# TSS_Rev3_Shield.net
KiCad netlist of a schematic drawn in EAGLE
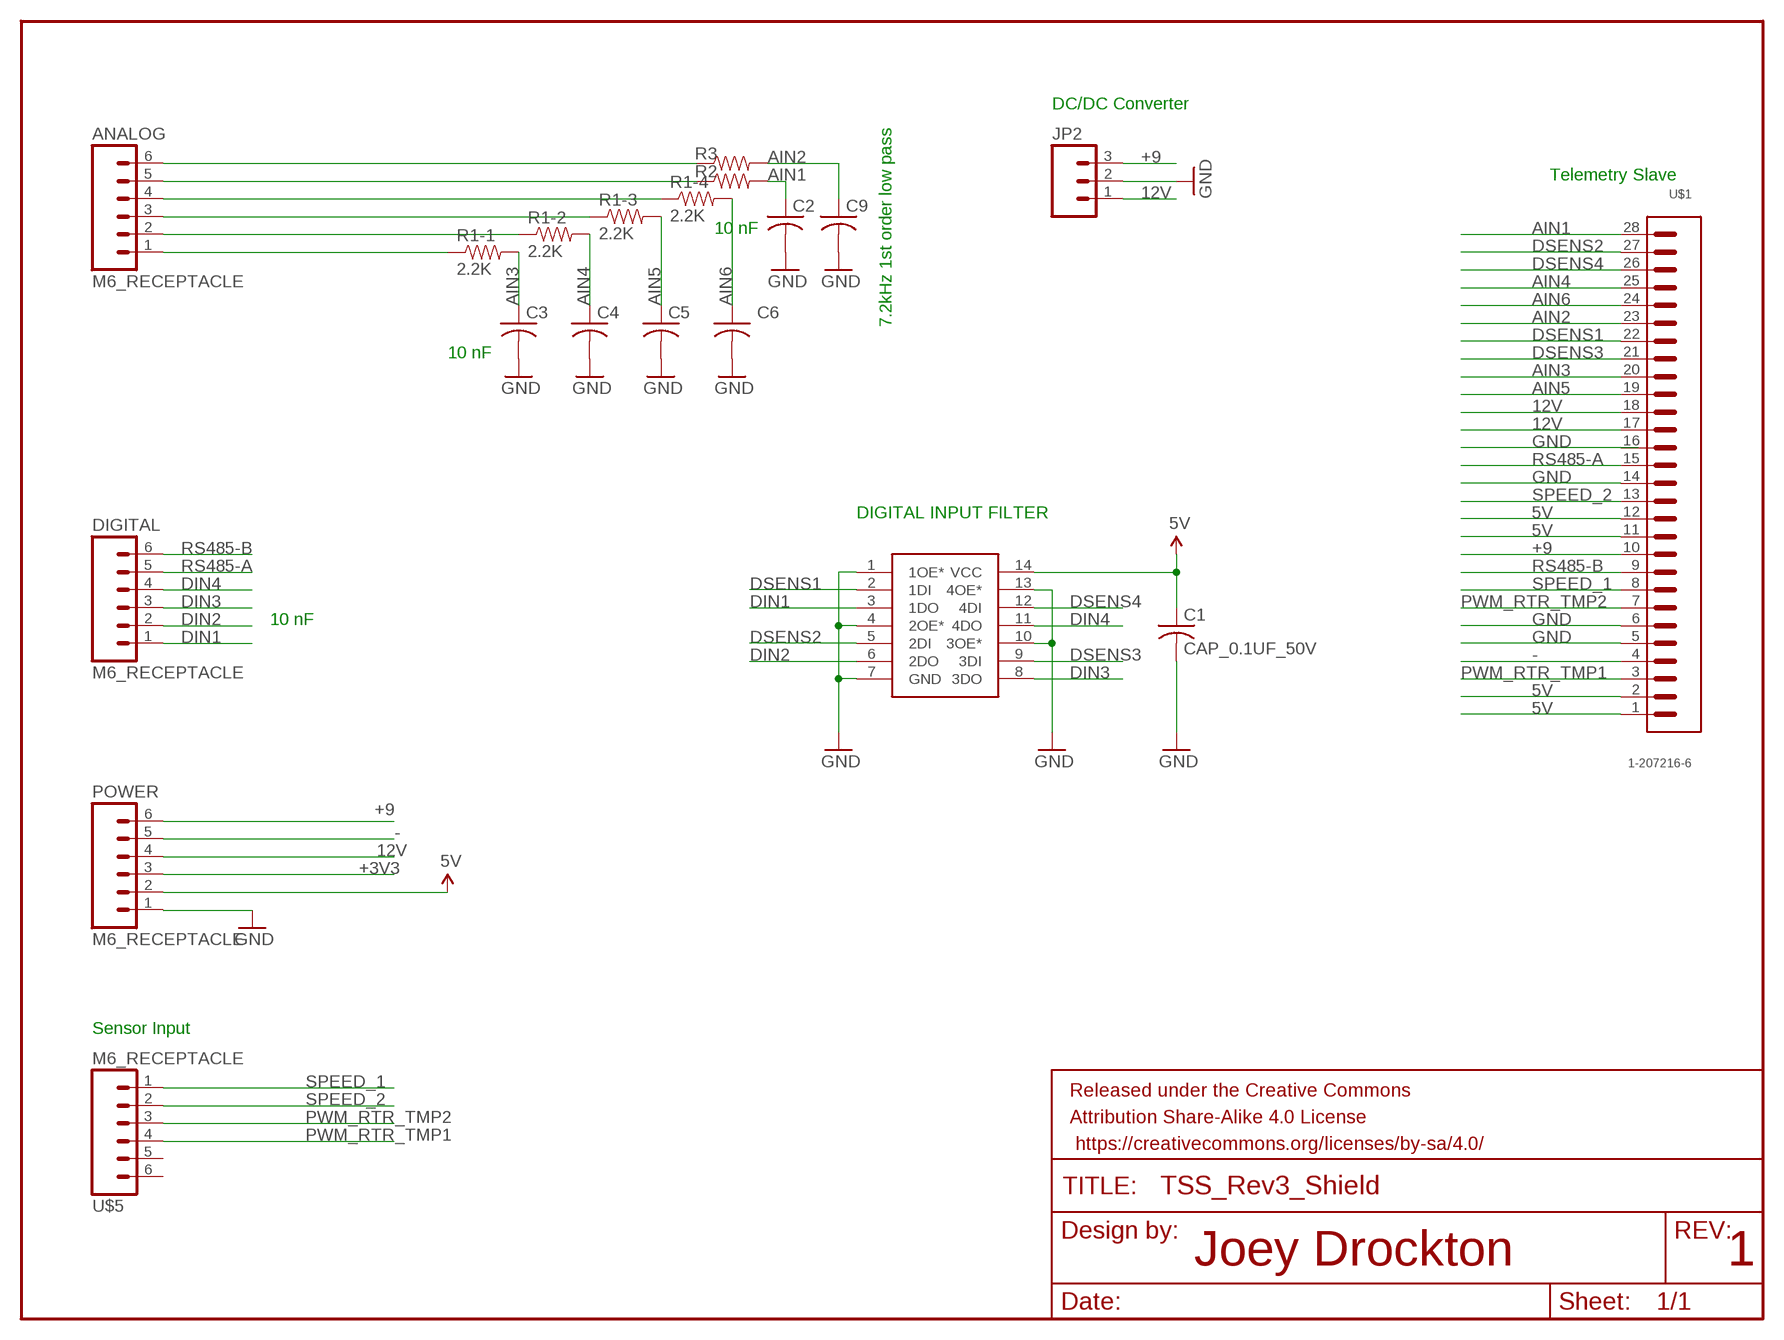
[diagram p0: schematic, sheet 1]

(export (version "E")
  (design (tool "Eeschema 10.0.6"))
  (components
    (comp (ref "ANALOG")
      (value "M6_RECEPTACLE")
      (footprint "eagle-import:6X.1")
      (fields (field (name "PARTNO") "A32907-ND"))
      (libsource (lib "eagle-import") (part "M6_RECEPTACLE"))
    )
    (comp (ref "C1")
      (value "CAP_0.1UF_50V")
      (footprint "eagle-import:0603")
      (fields (field (name "PARTNO") "CC0603ZRY5V9BB104"))
      (libsource (lib "eagle-import") (part "CAP_0.1UF_50V"))
    )
    (comp (ref "C2")
      (value "CAP_10NF_50V")
      (footprint "eagle-import:0603")
      (fields (field (name "PARTNO") "CL10F103ZB8NNNC"))
      (libsource (lib "eagle-import") (part "CAP_10NF_50V"))
    )
    (comp (ref "C3")
      (value "CAP_10NF_50V")
      (footprint "eagle-import:0603")
      (fields (field (name "PARTNO") "CL10F103ZB8NNNC"))
      (libsource (lib "eagle-import") (part "CAP_10NF_50V"))
    )
    (comp (ref "C4")
      (value "CAP_10NF_50V")
      (footprint "eagle-import:0603")
      (fields (field (name "PARTNO") "CL10F103ZB8NNNC"))
      (libsource (lib "eagle-import") (part "CAP_10NF_50V"))
    )
    (comp (ref "C5")
      (value "CAP_10NF_50V")
      (footprint "eagle-import:0603")
      (fields (field (name "PARTNO") "CL10F103ZB8NNNC"))
      (libsource (lib "eagle-import") (part "CAP_10NF_50V"))
    )
    (comp (ref "C6")
      (value "CAP_10NF_50V")
      (footprint "eagle-import:0603")
      (fields (field (name "PARTNO") "CL10F103ZB8NNNC"))
      (libsource (lib "eagle-import") (part "CAP_10NF_50V"))
    )
    (comp (ref "C9")
      (value "CAP_10NF_50V")
      (footprint "eagle-import:0603")
      (fields (field (name "PARTNO") "CL10F103ZB8NNNC"))
      (libsource (lib "eagle-import") (part "CAP_10NF_50V"))
    )
    (comp (ref "DIGITAL")
      (value "M6_RECEPTACLE")
      (footprint "eagle-import:6X.1")
      (fields (field (name "PARTNO") "A32907-ND"))
      (libsource (lib "eagle-import") (part "M6_RECEPTACLE"))
    )
    (comp (ref "FRAME1")
      (value "FRAME-LETTERNO_PACKAGE")
      (footprint "eagle-import:DUMMY")
      (fields (field (name "DESIGNER") "Nobody"))
      (libsource (lib "eagle-import") (part "FRAME-LETTERNO_PACKAGE"))
    )
    (comp (ref "JP2")
      (value "M03PTH")
      (footprint "eagle-import:1X03")
      (libsource (lib "eagle-import") (part "M03PTH"))
    )
    (comp (ref "POWER")
      (value "M6_RECEPTACLE")
      (footprint "eagle-import:6X.1")
      (fields (field (name "PARTNO") "A32907-ND"))
      (libsource (lib "eagle-import") (part "M6_RECEPTACLE"))
    )
    (comp (ref "R1")
      (value "2.2K")
      (footprint "eagle-import:MNR14")
      (fields (field (name "PARTNO") "MNR14ERAPJ222"))
      (libsource (lib "eagle-import") (part "RN-4_2.2K"))
    )
    (comp (ref "R2")
      (value "RES_2.2K_1%")
      (footprint "eagle-import:0603")
      (fields (field (name "PARTNO") "RC0603FR-072K2L"))
      (libsource (lib "eagle-import") (part "RES_2.2K_1%"))
    )
    (comp (ref "R3")
      (value "RES_2.2K_1%")
      (footprint "eagle-import:0603")
      (fields (field (name "PARTNO") "RC0603FR-072K2L"))
      (libsource (lib "eagle-import") (part "RES_2.2K_1%"))
    )
    (comp (ref "U$1")
      (value "1-207216-6")
      (footprint "eagle-import:1-207216-6")
      (libsource (lib "eagle-import") (part "1-207216-6"))
    )
    (comp (ref "U$2")
      (value "74HC125S14-13")
      (footprint "eagle-import:SO-14")
      (fields (field (name "PARTNO") " 74HC125S14-13DICT-ND"))
      (libsource (lib "eagle-import") (part "74HC125S14-13"))
    )
    (comp (ref "U$5")
      (value "M6_RECEPTACLE")
      (footprint "eagle-import:6X.1")
      (fields (field (name "PARTNO") "A32907-ND"))
      (libsource (lib "eagle-import") (part "M6_RECEPTACLE"))
    )
  )
  (nets
    (net (code "1") (name "/+3V3") (class "Default")
      (node (ref "POWER") (pin "3") (pinfunction "3_3") (pintype "passive"))
    )
    (net (code "2") (name "/+9") (class "Default")
      (node (ref "JP2") (pin "3") (pinfunction "3_3") (pintype "passive"))
      (node (ref "POWER") (pin "6") (pinfunction "6_6") (pintype "passive"))
      (node (ref "U$1") (pin "10") (pinfunction "P$10_10") (pintype "bidirectional"))
    )
    (net (code "3") (name "/-") (class "Default")
      (node (ref "POWER") (pin "5") (pinfunction "5_5") (pintype "passive"))
      (node (ref "U$1") (pin "4") (pinfunction "P$4_4") (pintype "bidirectional"))
    )
    (net (code "4") (name "/12V") (class "Default")
      (node (ref "JP2") (pin "1") (pinfunction "1_1") (pintype "passive"))
      (node (ref "POWER") (pin "4") (pinfunction "4_4") (pintype "passive"))
      (node (ref "U$1") (pin "17") (pinfunction "P$17_17") (pintype "bidirectional"))
      (node (ref "U$1") (pin "18") (pinfunction "P$18_18") (pintype "bidirectional"))
    )
    (net (code "5") (name "/AIN1") (class "Default")
      (node (ref "C2") (pin "1") (pinfunction "+_1") (pintype "passive"))
      (node (ref "R2") (pin "2") (pinfunction "2_2") (pintype "passive"))
      (node (ref "U$1") (pin "28") (pinfunction "P$28_28") (pintype "bidirectional"))
    )
    (net (code "6") (name "/AIN2") (class "Default")
      (node (ref "C9") (pin "1") (pinfunction "+_1") (pintype "passive"))
      (node (ref "R3") (pin "2") (pinfunction "2_2") (pintype "passive"))
      (node (ref "U$1") (pin "23") (pinfunction "P$23_23") (pintype "bidirectional"))
    )
    (net (code "7") (name "/AIN3") (class "Default")
      (node (ref "C3") (pin "1") (pinfunction "+_1") (pintype "passive"))
      (node (ref "R1") (pin "8") (pinfunction "2_8") (pintype "passive"))
      (node (ref "U$1") (pin "20") (pinfunction "P$20_20") (pintype "bidirectional"))
    )
    (net (code "8") (name "/AIN4") (class "Default")
      (node (ref "C4") (pin "1") (pinfunction "+_1") (pintype "passive"))
      (node (ref "R1") (pin "7") (pinfunction "2_7") (pintype "passive"))
      (node (ref "U$1") (pin "25") (pinfunction "P$25_25") (pintype "bidirectional"))
    )
    (net (code "9") (name "/AIN5") (class "Default")
      (node (ref "C5") (pin "1") (pinfunction "+_1") (pintype "passive"))
      (node (ref "R1") (pin "6") (pinfunction "2_6") (pintype "passive"))
      (node (ref "U$1") (pin "19") (pinfunction "P$19_19") (pintype "bidirectional"))
    )
    (net (code "10") (name "/AIN6") (class "Default")
      (node (ref "C6") (pin "1") (pinfunction "+_1") (pintype "passive"))
      (node (ref "R1") (pin "5") (pinfunction "2_5") (pintype "passive"))
      (node (ref "U$1") (pin "24") (pinfunction "P$24_24") (pintype "bidirectional"))
    )
    (net (code "11") (name "/DIN1") (class "Default")
      (node (ref "DIGITAL") (pin "1") (pinfunction "1_1") (pintype "passive"))
      (node (ref "U$2") (pin "3") (pinfunction "1DO_3") (pintype "bidirectional"))
    )
    (net (code "12") (name "/DIN2") (class "Default")
      (node (ref "DIGITAL") (pin "2") (pinfunction "2_2") (pintype "passive"))
      (node (ref "U$2") (pin "6") (pinfunction "2DO_6") (pintype "bidirectional"))
    )
    (net (code "13") (name "/DIN3") (class "Default")
      (node (ref "DIGITAL") (pin "3") (pinfunction "3_3") (pintype "passive"))
      (node (ref "U$2") (pin "8") (pinfunction "3DO_8") (pintype "bidirectional"))
    )
    (net (code "14") (name "/DIN4") (class "Default")
      (node (ref "DIGITAL") (pin "4") (pinfunction "4_4") (pintype "passive"))
      (node (ref "U$2") (pin "11") (pinfunction "4DO_11") (pintype "bidirectional"))
    )
    (net (code "15") (name "/DSENS1") (class "Default")
      (node (ref "U$1") (pin "22") (pinfunction "P$22_22") (pintype "bidirectional"))
      (node (ref "U$2") (pin "2") (pinfunction "1DI_2") (pintype "bidirectional"))
    )
    (net (code "16") (name "/DSENS2") (class "Default")
      (node (ref "U$1") (pin "27") (pinfunction "P$27_27") (pintype "bidirectional"))
      (node (ref "U$2") (pin "5") (pinfunction "2DI_5") (pintype "bidirectional"))
    )
    (net (code "17") (name "/DSENS3") (class "Default")
      (node (ref "U$1") (pin "21") (pinfunction "P$21_21") (pintype "bidirectional"))
      (node (ref "U$2") (pin "9") (pinfunction "3DI_9") (pintype "bidirectional"))
    )
    (net (code "18") (name "/DSENS4") (class "Default")
      (node (ref "U$1") (pin "26") (pinfunction "P$26_26") (pintype "bidirectional"))
      (node (ref "U$2") (pin "12") (pinfunction "4DI_12") (pintype "bidirectional"))
    )
    (net (code "19") (name "/PWM_RTR_TMP1") (class "Default")
      (node (ref "U$1") (pin "3") (pinfunction "P$3_3") (pintype "bidirectional"))
      (node (ref "U$5") (pin "4") (pinfunction "4_4") (pintype "passive"))
    )
    (net (code "20") (name "/PWM_RTR_TMP2") (class "Default")
      (node (ref "U$1") (pin "7") (pinfunction "P$7_7") (pintype "bidirectional"))
      (node (ref "U$5") (pin "3") (pinfunction "3_3") (pintype "passive"))
    )
    (net (code "21") (name "/RS485-A") (class "Default")
      (node (ref "DIGITAL") (pin "5") (pinfunction "5_5") (pintype "passive"))
      (node (ref "U$1") (pin "15") (pinfunction "P$15_15") (pintype "bidirectional"))
    )
    (net (code "22") (name "/RS485-B") (class "Default")
      (node (ref "DIGITAL") (pin "6") (pinfunction "6_6") (pintype "passive"))
      (node (ref "U$1") (pin "9") (pinfunction "P$9_9") (pintype "bidirectional"))
    )
    (net (code "23") (name "/SPEED_1") (class "Default")
      (node (ref "U$1") (pin "8") (pinfunction "P$8_8") (pintype "bidirectional"))
      (node (ref "U$5") (pin "1") (pinfunction "1_1") (pintype "passive"))
    )
    (net (code "24") (name "/SPEED_2") (class "Default")
      (node (ref "U$1") (pin "13") (pinfunction "P$13_13") (pintype "bidirectional"))
      (node (ref "U$5") (pin "2") (pinfunction "2_2") (pintype "passive"))
    )
    (net (code "25") (name "5V") (class "Default")
      (node (ref "C1") (pin "1") (pinfunction "+_1") (pintype "passive"))
      (node (ref "POWER") (pin "2") (pinfunction "2_2") (pintype "passive"))
      (node (ref "U$1") (pin "1") (pinfunction "P$1_1") (pintype "bidirectional"))
      (node (ref "U$1") (pin "11") (pinfunction "P$11_11") (pintype "bidirectional"))
      (node (ref "U$1") (pin "12") (pinfunction "P$12_12") (pintype "bidirectional"))
      (node (ref "U$1") (pin "2") (pinfunction "P$2_2") (pintype "bidirectional"))
      (node (ref "U$2") (pin "14") (pinfunction "VCC_14") (pintype "bidirectional"))
    )
    (net (code "26") (name "GND") (class "Default")
      (node (ref "C1") (pin "2") (pinfunction "-_2") (pintype "passive"))
      (node (ref "C2") (pin "2") (pinfunction "-_2") (pintype "passive"))
      (node (ref "C3") (pin "2") (pinfunction "-_2") (pintype "passive"))
      (node (ref "C4") (pin "2") (pinfunction "-_2") (pintype "passive"))
      (node (ref "C5") (pin "2") (pinfunction "-_2") (pintype "passive"))
      (node (ref "C6") (pin "2") (pinfunction "-_2") (pintype "passive"))
      (node (ref "C9") (pin "2") (pinfunction "-_2") (pintype "passive"))
      (node (ref "JP2") (pin "2") (pinfunction "2_2") (pintype "passive"))
      (node (ref "POWER") (pin "1") (pinfunction "1_1") (pintype "passive"))
      (node (ref "U$1") (pin "14") (pinfunction "P$14_14") (pintype "bidirectional"))
      (node (ref "U$1") (pin "16") (pinfunction "P$16_16") (pintype "bidirectional"))
      (node (ref "U$1") (pin "5") (pinfunction "P$5_5") (pintype "bidirectional"))
      (node (ref "U$1") (pin "6") (pinfunction "P$6_6") (pintype "bidirectional"))
      (node (ref "U$2") (pin "1") (pinfunction "1OE*_1") (pintype "bidirectional"))
      (node (ref "U$2") (pin "10") (pinfunction "3OE*_10") (pintype "bidirectional"))
      (node (ref "U$2") (pin "13") (pinfunction "4OE*_13") (pintype "bidirectional"))
      (node (ref "U$2") (pin "4") (pinfunction "2OE*_4") (pintype "bidirectional"))
      (node (ref "U$2") (pin "7") (pinfunction "GND_7") (pintype "bidirectional"))
    )
    (net (code "27") (name "Net-(ANALOG-Pad1)") (class "Default")
      (node (ref "ANALOG") (pin "1") (pinfunction "1_1") (pintype "passive"))
      (node (ref "R1") (pin "1") (pinfunction "1_1") (pintype "passive"))
    )
    (net (code "28") (name "Net-(ANALOG-Pad5)") (class "Default")
      (node (ref "ANALOG") (pin "5") (pinfunction "5_5") (pintype "passive"))
      (node (ref "R2") (pin "1") (pinfunction "1_1") (pintype "passive"))
    )
    (net (code "29") (name "Net-(ANALOG-Pad6)") (class "Default")
      (node (ref "ANALOG") (pin "6") (pinfunction "6_6") (pintype "passive"))
      (node (ref "R3") (pin "1") (pinfunction "1_1") (pintype "passive"))
    )
    (net (code "30") (name "Net-(R1B-1)") (class "Default")
      (node (ref "ANALOG") (pin "2") (pinfunction "2_2") (pintype "passive"))
      (node (ref "R1") (pin "2") (pinfunction "1_2") (pintype "passive"))
    )
    (net (code "31") (name "Net-(R1C-1)") (class "Default")
      (node (ref "ANALOG") (pin "3") (pinfunction "3_3") (pintype "passive"))
      (node (ref "R1") (pin "3") (pinfunction "1_3") (pintype "passive"))
    )
    (net (code "32") (name "Net-(R1D-1)") (class "Default")
      (node (ref "ANALOG") (pin "4") (pinfunction "4_4") (pintype "passive"))
      (node (ref "R1") (pin "4") (pinfunction "1_4") (pintype "passive"))
    )
    (net (code "33") (name "unconnected-(U$5-Pad5)") (class "Default")
      (node (ref "U$5") (pin "5") (pinfunction "5_5") (pintype "passive"))
    )
    (net (code "34") (name "unconnected-(U$5-Pad6)") (class "Default")
      (node (ref "U$5") (pin "6") (pinfunction "6_6") (pintype "passive"))
    )
  )
)
